# OSSI-1_LED_Panel.net
KiCad netlist of a schematic drawn in Altium Designer
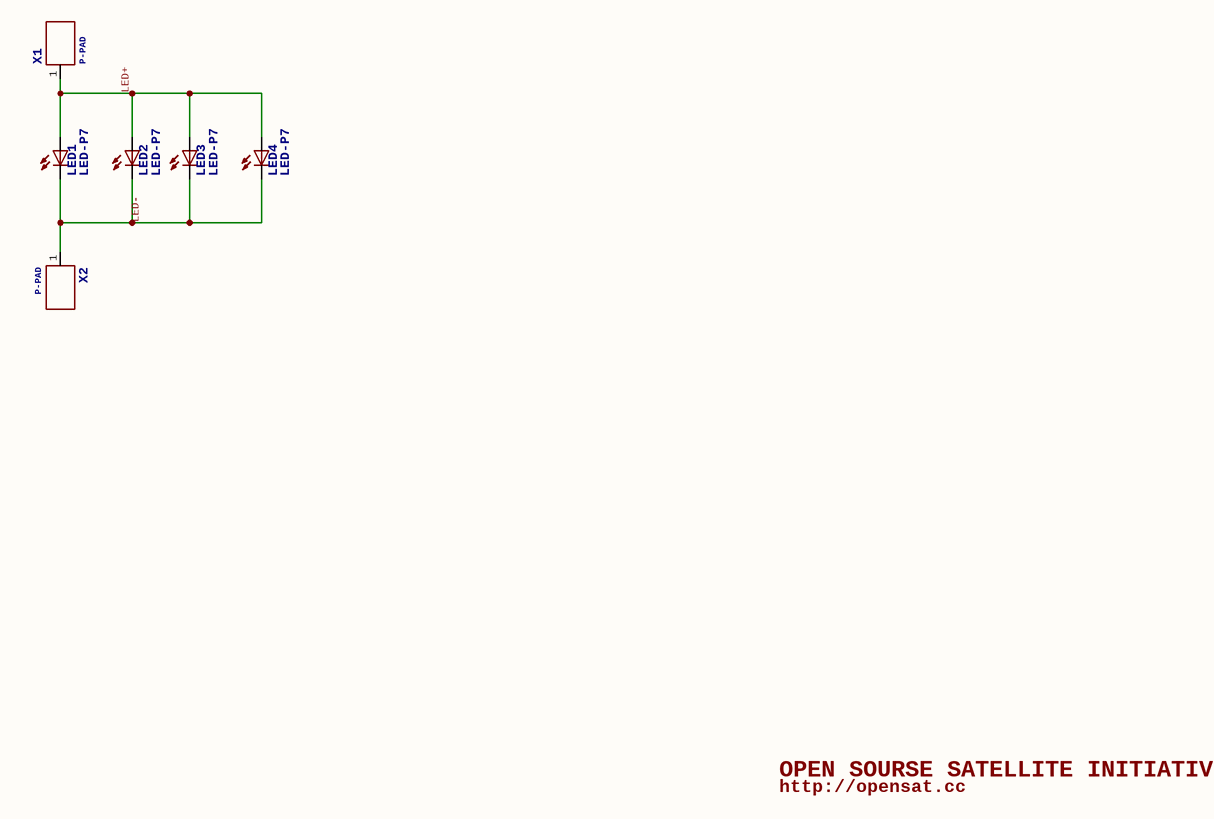
[diagram p0: OSSI-1 LED Panel.SchDoc]

(export (version "E")
  (design (tool "Eeschema 10.0.6"))
  (components
    (comp (ref "LED1")
      (value "LED-P7")
      (footprint "P7")
      (fields (field (name ">NAME") "LED1") (field (name ">VALUE") "LED-P7"))
      (libsource (lib "OSSI") (part "LED-P7"))
    )
    (comp (ref "LED2")
      (value "LED-P7")
      (footprint "P7")
      (fields (field (name ">NAME") "LED2") (field (name ">VALUE") "LED-P7"))
      (libsource (lib "OSSI") (part "LED-P7"))
    )
    (comp (ref "LED3")
      (value "LED-P7")
      (footprint "P7")
      (fields (field (name ">NAME") "LED3") (field (name ">VALUE") "LED-P7"))
      (libsource (lib "OSSI") (part "LED-P7"))
    )
    (comp (ref "LED4")
      (value "LED-P7")
      (footprint "P7")
      (fields (field (name ">NAME") "LED4") (field (name ">VALUE") "LED-P7"))
      (libsource (lib "OSSI") (part "LED-P7"))
    )
    (comp (ref "X1")
      (value "P-PAD")
      (footprint "P-PAD")
      (fields (field (name ">NAME") "X1") (field (name ">VALUE") "P-PAD"))
      (libsource (lib "OSSI") (part "P-PAD"))
    )
    (comp (ref "X2")
      (value "P-PAD")
      (footprint "P-PAD")
      (fields (field (name ">NAME") "X2") (field (name ">VALUE") "P-PAD"))
      (libsource (lib "OSSI") (part "P-PAD"))
    )
  )
  (nets
    (net (code "1") (name "/LED+") (class "Default")
      (node (ref "LED1") (pin "A") (pinfunction "A_A") (pintype "passive"))
      (node (ref "LED2") (pin "A") (pinfunction "A_A") (pintype "passive"))
      (node (ref "LED3") (pin "A") (pinfunction "A_A") (pintype "passive"))
      (node (ref "LED4") (pin "A") (pinfunction "A_A") (pintype "passive"))
      (node (ref "X1") (pin "1") (pinfunction "P$1_1") (pintype "passive"))
    )
    (net (code "2") (name "/LED-") (class "Default")
      (node (ref "LED1") (pin "C") (pinfunction "C_C") (pintype "passive"))
      (node (ref "LED2") (pin "C") (pinfunction "C_C") (pintype "passive"))
      (node (ref "LED3") (pin "C") (pinfunction "C_C") (pintype "passive"))
      (node (ref "LED4") (pin "C") (pinfunction "C_C") (pintype "passive"))
      (node (ref "X2") (pin "1") (pinfunction "P$1_1") (pintype "passive"))
    )
  )
)
